# ATtiny_Vario.net
KiCad netlist of a schematic drawn in EAGLE
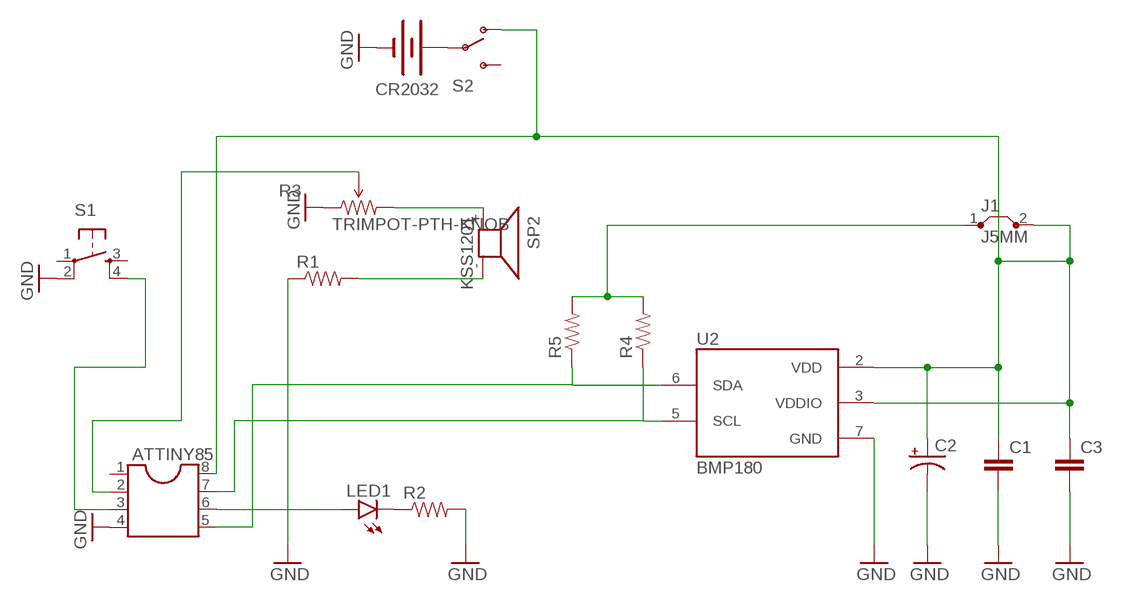
[diagram p0: schematic, sheet 1]

(export (version "E")
  (design (tool "Eeschema 10.0.6"))
  (components
    (comp (ref "ATTINY85")
      (value "DIL8S")
      (footprint "eagle-import:SOCKET-08")
      (libsource (lib "eagle-import") (part "DIL8S"))
    )
    (comp (ref "C1")
      (value "CAPPTH")
      (footprint "eagle-import:CAP-PTH-SMALL")
      (libsource (lib "eagle-import") (part "CAPPTH"))
    )
    (comp (ref "C2")
      (value "CAP_POLPTH2")
      (footprint "eagle-import:CPOL-RADIAL-10UF-25V")
      (libsource (lib "eagle-import") (part "CAP_POLPTH2"))
    )
    (comp (ref "C3")
      (value "CAPPTH")
      (footprint "eagle-import:CAP-PTH-SMALL")
      (libsource (lib "eagle-import") (part "CAPPTH"))
    )
    (comp (ref "CR2032")
      (value "BATTERY20PTH")
      (footprint "eagle-import:BATTCOM_20MM_PTH")
      (libsource (lib "eagle-import") (part "BATTERY20PTH"))
    )
    (comp (ref "J1")
      (value "J5MM")
      (footprint "eagle-import:05")
      (libsource (lib "eagle-import") (part "J5MM"))
    )
    (comp (ref "LED1")
      (value "LED3MM")
      (footprint "eagle-import:LED3MM")
      (libsource (lib "eagle-import") (part "LED3MM"))
    )
    (comp (ref "R1")
      (value "RESISTOREZ")
      (footprint "eagle-import:AXIAL-0.3EZ")
      (libsource (lib "eagle-import") (part "RESISTOREZ"))
    )
    (comp (ref "R2")
      (value "RESISTORPTH-1/6W")
      (footprint "eagle-import:1_6W-RES")
      (libsource (lib "eagle-import") (part "RESISTORPTH-1/6W"))
    )
    (comp (ref "R3")
      (value "TRIMPOT-PTH-KNOB")
      (footprint "eagle-import:3386U")
      (libsource (lib "eagle-import") (part "TRIMPOT-PTH-KNOB"))
    )
    (comp (ref "R4")
      (value "RESISTOREZ")
      (footprint "eagle-import:AXIAL-0.3EZ")
      (libsource (lib "eagle-import") (part "RESISTOREZ"))
    )
    (comp (ref "R5")
      (value "RESISTOREZ")
      (footprint "eagle-import:AXIAL-0.3EZ")
      (libsource (lib "eagle-import") (part "RESISTOREZ"))
    )
    (comp (ref "S1")
      (value "TAC_SWITCHPTH")
      (footprint "eagle-import:TACTILE-PTH")
      (libsource (lib "eagle-import") (part "TAC_SWITCHPTH"))
    )
    (comp (ref "S2")
      (value "SWITCH-SPDTPTH")
      (footprint "eagle-import:SWITCH-SPDT")
      (libsource (lib "eagle-import") (part "SWITCH-SPDTPTH"))
    )
    (comp (ref "SP2")
      (value "KSS1201")
      (footprint "eagle-import:KSS1201")
      (libsource (lib "eagle-import") (part "KSS1201"))
    )
    (comp (ref "U2")
      (value "BMP180")
      (footprint "eagle-import:BMP180")
      (libsource (lib "eagle-import") (part "BMP180"))
    )
  )
  (nets
    (net (code "1") (name "GND") (class "Default")
      (node (ref "ATTINY85") (pin "4") (pinfunction "4_4") (pintype "passive"))
      (node (ref "C1") (pin "2") (pinfunction "2_2") (pintype "passive"))
      (node (ref "C2") (pin "2") (pinfunction "-_2") (pintype "passive"))
      (node (ref "C3") (pin "2") (pinfunction "2_2") (pintype "passive"))
      (node (ref "CR2032") (pin "2") (pinfunction "-_2") (pintype "power_in"))
      (node (ref "R1") (pin "P$1") (pinfunction "1_P$1") (pintype "passive"))
      (node (ref "R2") (pin "2") (pinfunction "2_2") (pintype "passive"))
      (node (ref "R3") (pin "1") (pinfunction "CCW_1") (pintype "passive"))
      (node (ref "S1") (pin "2") (pinfunction "2_2") (pintype "passive"))
      (node (ref "U2") (pin "7") (pinfunction "GND_7") (pintype "power_in"))
    )
    (net (code "2") (name "Net-(ATTINY85-Pad3)") (class "Default")
      (node (ref "ATTINY85") (pin "3") (pinfunction "3_3") (pintype "passive"))
      (node (ref "S1") (pin "4") (pinfunction "4_4") (pintype "passive"))
    )
    (net (code "3") (name "Net-(ATTINY85-Pad6)") (class "Default")
      (node (ref "ATTINY85") (pin "6") (pinfunction "6_6") (pintype "passive"))
      (node (ref "LED1") (pin "A") (pinfunction "A_A") (pintype "passive"))
    )
    (net (code "4") (name "Net-(C2-+)") (class "Default")
      (node (ref "ATTINY85") (pin "8") (pinfunction "8_8") (pintype "passive"))
      (node (ref "C1") (pin "1") (pinfunction "1_1") (pintype "passive"))
      (node (ref "C2") (pin "1") (pinfunction "+_1") (pintype "passive"))
      (node (ref "C3") (pin "1") (pinfunction "1_1") (pintype "passive"))
      (node (ref "J1") (pin "2") (pinfunction "2_2") (pintype "passive"))
      (node (ref "S2") (pin "1") (pinfunction "O_1") (pintype "passive"))
      (node (ref "U2") (pin "2") (pinfunction "VDD_2") (pintype "power_in"))
      (node (ref "U2") (pin "3") (pinfunction "VDDIO_3") (pintype "power_in"))
    )
    (net (code "5") (name "Net-(CR2032-+)") (class "Default")
      (node (ref "CR2032") (pin "1") (pinfunction "+_1") (pintype "power_in"))
      (node (ref "S2") (pin "2") (pinfunction "P_2") (pintype "passive"))
    )
    (net (code "6") (name "Net-(LED1-C)") (class "Default")
      (node (ref "LED1") (pin "K") (pinfunction "C_K") (pintype "passive"))
      (node (ref "R2") (pin "1") (pinfunction "1_1") (pintype "passive"))
    )
    (net (code "7") (name "Net-(R1-2)") (class "Default")
      (node (ref "R1") (pin "P$2") (pinfunction "2_P$2") (pintype "passive"))
      (node (ref "SP2") (pin "-") (pinfunction "2_-") (pintype "passive"))
    )
    (net (code "8") (name "Net-(R3-CW)") (class "Default")
      (node (ref "R3") (pin "3") (pinfunction "CW_3") (pintype "passive"))
      (node (ref "SP2") (pin "+") (pinfunction "1_+") (pintype "passive"))
    )
    (net (code "9") (name "Net-(R3-WIPER)") (class "Default")
      (node (ref "ATTINY85") (pin "2") (pinfunction "2_2") (pintype "passive"))
      (node (ref "R3") (pin "2") (pinfunction "WIPER_2") (pintype "passive"))
    )
    (net (code "10") (name "Net-(R4-1)") (class "Default")
      (node (ref "ATTINY85") (pin "7") (pinfunction "7_7") (pintype "passive"))
      (node (ref "R4") (pin "P$1") (pinfunction "1_P$1") (pintype "passive"))
      (node (ref "U2") (pin "5") (pinfunction "SCL_5") (pintype "input"))
    )
    (net (code "11") (name "Net-(R4-2)") (class "Default")
      (node (ref "J1") (pin "1") (pinfunction "1_1") (pintype "passive"))
      (node (ref "R4") (pin "P$2") (pinfunction "2_P$2") (pintype "passive"))
      (node (ref "R5") (pin "P$2") (pinfunction "2_P$2") (pintype "passive"))
    )
    (net (code "12") (name "Net-(R5-1)") (class "Default")
      (node (ref "ATTINY85") (pin "5") (pinfunction "5_5") (pintype "passive"))
      (node (ref "R5") (pin "P$1") (pinfunction "1_P$1") (pintype "passive"))
      (node (ref "U2") (pin "6") (pinfunction "SDA_6") (pintype "bidirectional"))
    )
    (net (code "13") (name "unconnected-(ATTINY85-Pad1)") (class "Default")
      (node (ref "ATTINY85") (pin "1") (pinfunction "1_1") (pintype "passive"))
    )
    (net (code "14") (name "unconnected-(S1-Pad1)") (class "Default")
      (node (ref "S1") (pin "1") (pinfunction "1_1") (pintype "passive"))
    )
    (net (code "15") (name "unconnected-(S1-Pad3)") (class "Default")
      (node (ref "S1") (pin "3") (pinfunction "3_3") (pintype "passive"))
    )
    (net (code "16") (name "unconnected-(S2-S-Pad3)") (class "Default")
      (node (ref "S2") (pin "3") (pinfunction "S_3") (pintype "passive"))
    )
  )
)
